# Puzzle_-_Button_v1.net
KiCad netlist of a schematic drawn in EAGLE
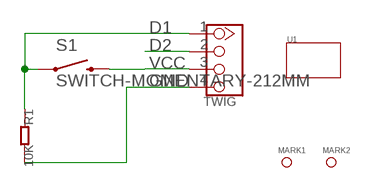
[diagram p0: schematic, sheet 1]

(export (version "E")
  (design (tool "Eeschema 10.0.6"))
  (components
    (comp (ref "J1")
      (value "TWIG")
      (footprint "eagle-import:4P-LEADED-2.0")
      (libsource (lib "eagle-import") (part "TWIG-2.0-LEADED-2.0"))
    )
    (comp (ref "MARK1")
      (value "PAD-MARK")
      (footprint "eagle-import:ROUND-MARK-0.635")
      (libsource (lib "eagle-import") (part "PAD-MARK"))
    )
    (comp (ref "MARK2")
      (value "PAD-MARK")
      (footprint "eagle-import:ROUND-MARK-0.635")
      (libsource (lib "eagle-import") (part "PAD-MARK"))
    )
    (comp (ref "R1")
      (value "10K")
      (footprint "eagle-import:0603")
      (libsource (lib "eagle-import") (part "R-0603"))
    )
    (comp (ref "S1")
      (value "SWITCH-MOMENTARY-212MM")
      (footprint "eagle-import:TACTILE-PTH-12MM")
      (libsource (lib "eagle-import") (part "SWITCH-MOMENTARY-212MM"))
    )
    (comp (ref "U1")
      (value "TWIG-1U")
      (footprint "eagle-import:1U-DIM-W_-DRILL")
      (libsource (lib "eagle-import") (part "TWIG-1U"))
    )
  )
  (nets
    (net (code "1") (name "/D1") (class "Default")
      (node (ref "J1") (pin "1") (pinfunction "1_1") (pintype "bidirectional"))
      (node (ref "R1") (pin "1") (pinfunction "1_1") (pintype "passive"))
      (node (ref "S1") (pin "1") (pinfunction "1_1") (pintype "passive"))
    )
    (net (code "2") (name "/D2") (class "Default")
      (node (ref "J1") (pin "2") (pinfunction "2_2") (pintype "bidirectional"))
    )
    (net (code "3") (name "/GND") (class "Default")
      (node (ref "J1") (pin "4") (pinfunction "4_4") (pintype "bidirectional"))
      (node (ref "R1") (pin "2") (pinfunction "2_2") (pintype "passive"))
    )
    (net (code "4") (name "/VCC") (class "Default")
      (node (ref "J1") (pin "3") (pinfunction "3_3") (pintype "bidirectional"))
      (node (ref "S1") (pin "3") (pinfunction "2_3") (pintype "passive"))
    )
  )
)
